# drownAlert_try1.net
KiCad netlist of a schematic drawn in EAGLE
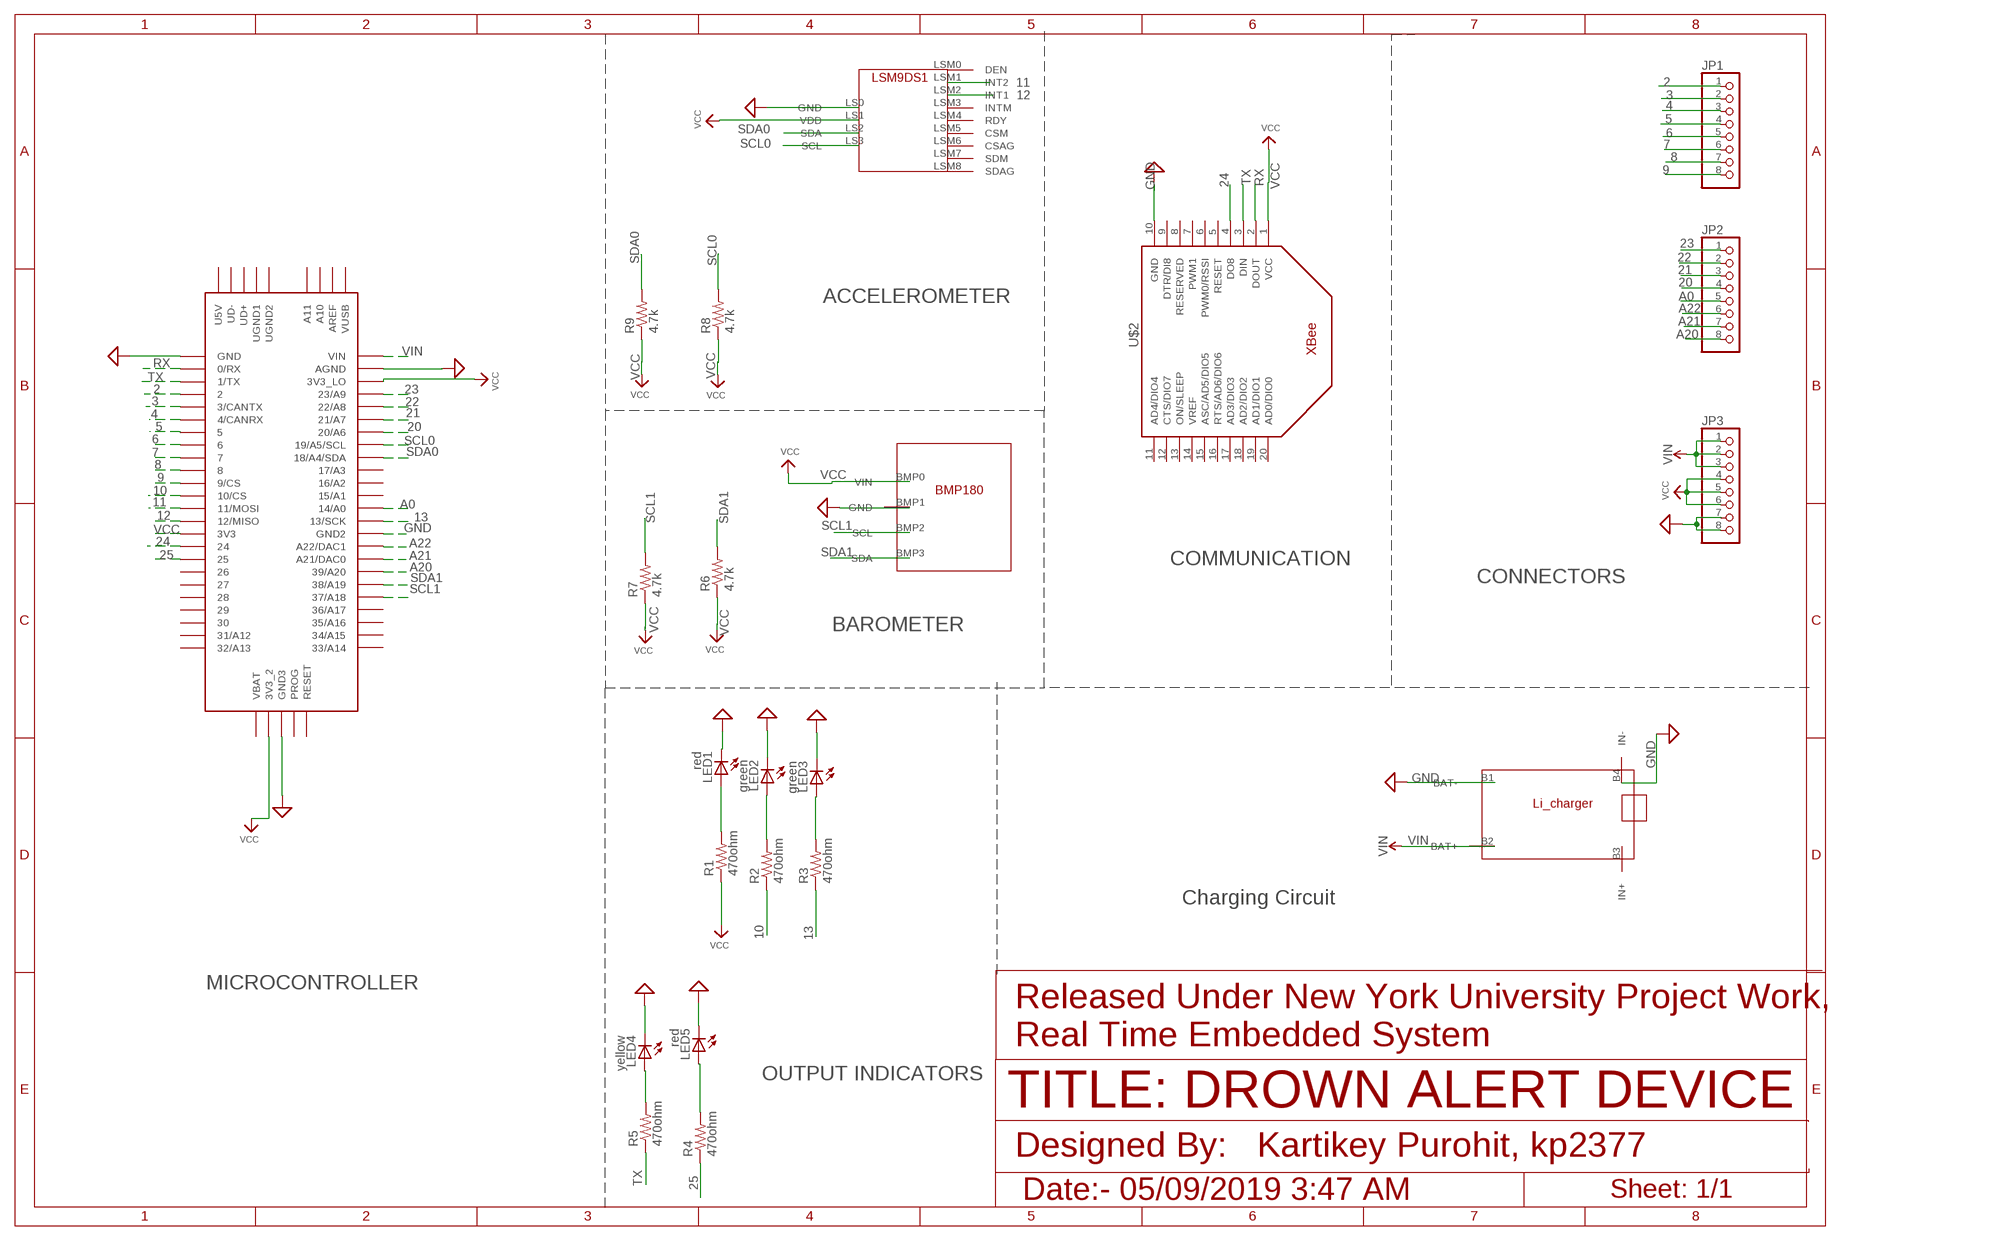
[diagram p0: schematic, sheet 1]

(export (version "E")
  (design (tool "Eeschema 10.0.6"))
  (components
    (comp (ref "JP1")
      (value "PINHD-1X8-3.5MM")
      (footprint "eagle-import:1X08-3.5MM")
      (libsource (lib "eagle-import") (part "PINHD-1X8-3.5MM"))
    )
    (comp (ref "JP2")
      (value "PINHD-1X8-3.5MM")
      (footprint "eagle-import:1X08-3.5MM")
      (libsource (lib "eagle-import") (part "PINHD-1X8-3.5MM"))
    )
    (comp (ref "JP3")
      (value "PINHD-1X8-3.5MM")
      (footprint "eagle-import:1X08-3.5MM")
      (libsource (lib "eagle-import") (part "PINHD-1X8-3.5MM"))
    )
    (comp (ref "LED1")
      (value "red")
      (footprint "eagle-import:CHIPLED_1206")
      (libsource (lib "eagle-import") (part "LEDCHIPLED_1206"))
    )
    (comp (ref "LED2")
      (value "green")
      (footprint "eagle-import:CHIPLED_1206")
      (libsource (lib "eagle-import") (part "LEDCHIPLED_1206"))
    )
    (comp (ref "LED3")
      (value "green")
      (footprint "eagle-import:CHIPLED_1206")
      (libsource (lib "eagle-import") (part "LEDCHIPLED_1206"))
    )
    (comp (ref "LED4")
      (value "yellow")
      (footprint "eagle-import:CHIPLED_1206")
      (libsource (lib "eagle-import") (part "LEDCHIPLED_1206"))
    )
    (comp (ref "LED5")
      (value "red")
      (footprint "eagle-import:CHIPLED_1206")
      (libsource (lib "eagle-import") (part "LEDCHIPLED_1206"))
    )
    (comp (ref "R1")
      (value "470ohm")
      (footprint "eagle-import:R1206")
      (libsource (lib "eagle-import") (part "R-US_R1206"))
    )
    (comp (ref "R2")
      (value "470ohm")
      (footprint "eagle-import:R1206")
      (libsource (lib "eagle-import") (part "R-US_R1206"))
    )
    (comp (ref "R3")
      (value "470ohm")
      (footprint "eagle-import:R1206")
      (libsource (lib "eagle-import") (part "R-US_R1206"))
    )
    (comp (ref "R4")
      (value "470ohm")
      (footprint "eagle-import:R1206")
      (libsource (lib "eagle-import") (part "R-US_R1206"))
    )
    (comp (ref "R5")
      (value "470ohm")
      (footprint "eagle-import:R1206")
      (libsource (lib "eagle-import") (part "R-US_R1206"))
    )
    (comp (ref "R6")
      (value "4.7k")
      (footprint "eagle-import:R1206")
      (libsource (lib "eagle-import") (part "R-US_R1206"))
    )
    (comp (ref "R7")
      (value "4.7k")
      (footprint "eagle-import:R1206")
      (libsource (lib "eagle-import") (part "R-US_R1206"))
    )
    (comp (ref "R8")
      (value "4.7k")
      (footprint "eagle-import:R1206")
      (libsource (lib "eagle-import") (part "R-US_R1206"))
    )
    (comp (ref "R9")
      (value "4.7k")
      (footprint "eagle-import:R1206")
      (libsource (lib "eagle-import") (part "R-US_R1206"))
    )
    (comp (ref "U$1")
      (value "TEENSY_3.5/3.6")
      (footprint "eagle-import:TEENSY_3.5_3.6")
      (libsource (lib "eagle-import") (part "TEENSY_3.5/3.6"))
    )
    (comp (ref "U$2")
      (value "XBEE")
      (footprint "eagle-import:XBEE")
      (libsource (lib "eagle-import") (part "XBEE"))
    )
    (comp (ref "U$3")
      (value "KKP_BATTERY_CHARGER")
      (footprint "eagle-import:KKP_CUSTOM_BATTERY_CHARGER")
      (libsource (lib "eagle-import") (part "KKP_BATTERY_CHARGER"))
    )
    (comp (ref "U$5")
      (value "KKP_BMP180")
      (footprint "eagle-import:KKP_CUSTOM_BMP180")
      (libsource (lib "eagle-import") (part "KKP_BMP180"))
    )
    (comp (ref "U$6")
      (value "KKP_LSM")
      (footprint "eagle-import:KKP_CUSTOM_LSM9D-S1_FOOTPRINT")
      (libsource (lib "eagle-import") (part "KKP_LSM"))
    )
  )
  (nets
    (net (code "1") (name "/2") (class "Default")
      (node (ref "JP1") (pin "1") (pinfunction "1_1") (pintype "passive"))
      (node (ref "U$1") (pin "2") (pinfunction "2_2") (pintype "bidirectional"))
    )
    (net (code "2") (name "/3") (class "Default")
      (node (ref "JP1") (pin "2") (pinfunction "2_2") (pintype "passive"))
      (node (ref "U$1") (pin "3/CANTX") (pinfunction "3/CANTX_3/CANTX") (pintype "bidirectional"))
    )
    (net (code "3") (name "/4") (class "Default")
      (node (ref "JP1") (pin "3") (pinfunction "3_3") (pintype "passive"))
      (node (ref "U$1") (pin "4/CANRX") (pinfunction "4/CANRX_4/CANRX") (pintype "bidirectional"))
    )
    (net (code "4") (name "/5") (class "Default")
      (node (ref "JP1") (pin "4") (pinfunction "4_4") (pintype "passive"))
      (node (ref "U$1") (pin "5") (pinfunction "5_5") (pintype "bidirectional"))
    )
    (net (code "5") (name "/6") (class "Default")
      (node (ref "JP1") (pin "5") (pinfunction "5_5") (pintype "passive"))
      (node (ref "U$1") (pin "6") (pinfunction "6_6") (pintype "bidirectional"))
    )
    (net (code "6") (name "/7") (class "Default")
      (node (ref "JP1") (pin "6") (pinfunction "6_6") (pintype "passive"))
      (node (ref "U$1") (pin "7") (pinfunction "7_7") (pintype "bidirectional"))
    )
    (net (code "7") (name "/8") (class "Default")
      (node (ref "JP1") (pin "7") (pinfunction "7_7") (pintype "passive"))
      (node (ref "U$1") (pin "8") (pinfunction "8_8") (pintype "bidirectional"))
    )
    (net (code "8") (name "/9") (class "Default")
      (node (ref "JP1") (pin "8") (pinfunction "8_8") (pintype "passive"))
      (node (ref "U$1") (pin "9/CS") (pinfunction "9/CS_9/CS") (pintype "bidirectional"))
    )
    (net (code "9") (name "/10") (class "Default")
      (node (ref "R2") (pin "1") (pinfunction "1_1") (pintype "passive"))
      (node (ref "U$1") (pin "10/CS") (pinfunction "10/CS_10/CS") (pintype "bidirectional"))
    )
    (net (code "10") (name "/11") (class "Default")
      (node (ref "U$1") (pin "11/MOSI") (pinfunction "11/MOSI_11/MOSI") (pintype "bidirectional"))
      (node (ref "U$6") (pin "LSM1") (pinfunction "INT2_LSM1") (pintype "bidirectional"))
    )
    (net (code "11") (name "/12") (class "Default")
      (node (ref "U$1") (pin "12/MISO") (pinfunction "12/MISO_12/MISO") (pintype "bidirectional"))
      (node (ref "U$6") (pin "LSM2") (pinfunction "INT1_LSM2") (pintype "bidirectional"))
    )
    (net (code "12") (name "/13") (class "Default")
      (node (ref "R3") (pin "1") (pinfunction "1_1") (pintype "passive"))
      (node (ref "U$1") (pin "13/SCK") (pinfunction "13/SCK_13/SCK") (pintype "bidirectional"))
    )
    (net (code "13") (name "/20") (class "Default")
      (node (ref "JP2") (pin "4") (pinfunction "4_4") (pintype "passive"))
      (node (ref "U$1") (pin "20/A6") (pinfunction "20/A6_20/A6") (pintype "bidirectional"))
    )
    (net (code "14") (name "/21") (class "Default")
      (node (ref "JP2") (pin "3") (pinfunction "3_3") (pintype "passive"))
      (node (ref "U$1") (pin "21/A7") (pinfunction "21/A7_21/A7") (pintype "bidirectional"))
    )
    (net (code "15") (name "/22") (class "Default")
      (node (ref "JP2") (pin "2") (pinfunction "2_2") (pintype "passive"))
      (node (ref "U$1") (pin "22/A8") (pinfunction "22/A8_22/A8") (pintype "bidirectional"))
    )
    (net (code "16") (name "/23") (class "Default")
      (node (ref "JP2") (pin "1") (pinfunction "1_1") (pintype "passive"))
      (node (ref "U$1") (pin "23/A9") (pinfunction "23/A9_23/A9") (pintype "bidirectional"))
    )
    (net (code "17") (name "/24") (class "Default")
      (node (ref "U$1") (pin "24") (pinfunction "24_24") (pintype "bidirectional"))
      (node (ref "U$2") (pin "4") (pinfunction "DO8_4") (pintype "output"))
    )
    (net (code "18") (name "/25") (class "Default")
      (node (ref "R4") (pin "1") (pinfunction "1_1") (pintype "passive"))
      (node (ref "U$1") (pin "25") (pinfunction "25_25") (pintype "bidirectional"))
    )
    (net (code "19") (name "/A0") (class "Default")
      (node (ref "JP2") (pin "5") (pinfunction "5_5") (pintype "passive"))
      (node (ref "U$1") (pin "14/A0") (pinfunction "14/A0_14/A0") (pintype "bidirectional"))
    )
    (net (code "20") (name "/A20") (class "Default")
      (node (ref "JP2") (pin "8") (pinfunction "8_8") (pintype "passive"))
      (node (ref "U$1") (pin "39/A20") (pinfunction "39/A20_39/A20") (pintype "bidirectional"))
    )
    (net (code "21") (name "/A21") (class "Default")
      (node (ref "JP2") (pin "7") (pinfunction "7_7") (pintype "passive"))
      (node (ref "U$1") (pin "21/DAC0") (pinfunction "A21/DAC0_21/DAC0") (pintype "bidirectional"))
    )
    (net (code "22") (name "/A22") (class "Default")
      (node (ref "JP2") (pin "6") (pinfunction "6_6") (pintype "passive"))
      (node (ref "U$1") (pin "A22/DAC1") (pinfunction "A22/DAC1_A22/DAC1") (pintype "bidirectional"))
    )
    (net (code "23") (name "/RX") (class "Default")
      (node (ref "U$1") (pin "0/RX") (pinfunction "0/RX_0/RX") (pintype "bidirectional"))
      (node (ref "U$2") (pin "2") (pinfunction "DOUT_2") (pintype "output"))
    )
    (net (code "24") (name "/SCL0") (class "Default")
      (node (ref "R8") (pin "2") (pinfunction "2_2") (pintype "passive"))
      (node (ref "U$1") (pin "19/A5/SCL") (pinfunction "19/A5/SCL_19/A5/SCL") (pintype "bidirectional"))
      (node (ref "U$6") (pin "LS3") (pinfunction "SCL_LS3") (pintype "bidirectional"))
    )
    (net (code "25") (name "/SCL1") (class "Default")
      (node (ref "R7") (pin "2") (pinfunction "2_2") (pintype "passive"))
      (node (ref "U$1") (pin "37/A18") (pinfunction "37/A18_37/A18") (pintype "bidirectional"))
      (node (ref "U$5") (pin "BMP2") (pinfunction "SCL_BMP2") (pintype "bidirectional"))
    )
    (net (code "26") (name "/SDA0") (class "Default")
      (node (ref "R9") (pin "2") (pinfunction "2_2") (pintype "passive"))
      (node (ref "U$1") (pin "18/A4/SDA") (pinfunction "18/A4/SDA_18/A4/SDA") (pintype "bidirectional"))
      (node (ref "U$6") (pin "LS2") (pinfunction "SDA_LS2") (pintype "bidirectional"))
    )
    (net (code "27") (name "/SDA1") (class "Default")
      (node (ref "R6") (pin "2") (pinfunction "2_2") (pintype "passive"))
      (node (ref "U$1") (pin "38/A19") (pinfunction "38/A19_38/A19") (pintype "bidirectional"))
      (node (ref "U$5") (pin "BMP3") (pinfunction "SDA_BMP3") (pintype "bidirectional"))
    )
    (net (code "28") (name "/TX") (class "Default")
      (node (ref "R5") (pin "1") (pinfunction "1_1") (pintype "passive"))
      (node (ref "U$1") (pin "1/TX") (pinfunction "1/TX_1/TX") (pintype "bidirectional"))
      (node (ref "U$2") (pin "3") (pinfunction "DIN_3") (pintype "input"))
    )
    (net (code "29") (name "Net-(LED1-PadA)") (class "Default")
      (node (ref "LED1") (pin "A") (pinfunction "A_A") (pintype "passive"))
      (node (ref "R1") (pin "2") (pinfunction "2_2") (pintype "passive"))
    )
    (net (code "30") (name "Net-(LED2-PadA)") (class "Default")
      (node (ref "LED2") (pin "A") (pinfunction "A_A") (pintype "passive"))
      (node (ref "R2") (pin "2") (pinfunction "2_2") (pintype "passive"))
    )
    (net (code "31") (name "Net-(LED3-PadA)") (class "Default")
      (node (ref "LED3") (pin "A") (pinfunction "A_A") (pintype "passive"))
      (node (ref "R3") (pin "2") (pinfunction "2_2") (pintype "passive"))
    )
    (net (code "32") (name "Net-(LED4-PadA)") (class "Default")
      (node (ref "LED4") (pin "A") (pinfunction "A_A") (pintype "passive"))
      (node (ref "R5") (pin "2") (pinfunction "2_2") (pintype "passive"))
    )
    (net (code "33") (name "Net-(LED5-PadA)") (class "Default")
      (node (ref "LED5") (pin "A") (pinfunction "A_A") (pintype "passive"))
      (node (ref "R4") (pin "2") (pinfunction "2_2") (pintype "passive"))
    )
    (net (code "34") (name "SUP") (class "Default")
      (node (ref "JP3") (pin "7") (pinfunction "7_7") (pintype "passive"))
      (node (ref "JP3") (pin "8") (pinfunction "8_8") (pintype "passive"))
      (node (ref "LED1") (pin "C") (pinfunction "C_C") (pintype "passive"))
      (node (ref "LED2") (pin "C") (pinfunction "C_C") (pintype "passive"))
      (node (ref "LED3") (pin "C") (pinfunction "C_C") (pintype "passive"))
      (node (ref "LED4") (pin "C") (pinfunction "C_C") (pintype "passive"))
      (node (ref "LED5") (pin "C") (pinfunction "C_C") (pintype "passive"))
      (node (ref "U$1") (pin "AGND") (pinfunction "AGND_AGND") (pintype "bidirectional"))
      (node (ref "U$1") (pin "GND") (pinfunction "GND_GND") (pintype "bidirectional"))
      (node (ref "U$1") (pin "GND2") (pinfunction "GND2_GND2") (pintype "bidirectional"))
      (node (ref "U$1") (pin "GND3") (pinfunction "GND3_GND3") (pintype "bidirectional"))
      (node (ref "U$2") (pin "10") (pinfunction "GND_10") (pintype "power_in"))
      (node (ref "U$3") (pin "B1") (pinfunction "BAT-_B1") (pintype "bidirectional"))
      (node (ref "U$3") (pin "B4") (pinfunction "IN-_B4") (pintype "bidirectional"))
      (node (ref "U$5") (pin "BMP1") (pinfunction "GND_BMP1") (pintype "bidirectional"))
      (node (ref "U$6") (pin "LS0") (pinfunction "GND_LS0") (pintype "bidirectional"))
    )
    (net (code "35") (name "VCC") (class "Default")
      (node (ref "JP3") (pin "4") (pinfunction "4_4") (pintype "passive"))
      (node (ref "JP3") (pin "5") (pinfunction "5_5") (pintype "passive"))
      (node (ref "JP3") (pin "6") (pinfunction "6_6") (pintype "passive"))
      (node (ref "R1") (pin "1") (pinfunction "1_1") (pintype "passive"))
      (node (ref "R6") (pin "1") (pinfunction "1_1") (pintype "passive"))
      (node (ref "R7") (pin "1") (pinfunction "1_1") (pintype "passive"))
      (node (ref "R8") (pin "1") (pinfunction "1_1") (pintype "passive"))
      (node (ref "R9") (pin "1") (pinfunction "1_1") (pintype "passive"))
      (node (ref "U$1") (pin "3V3") (pinfunction "3V3_3V3") (pintype "bidirectional"))
      (node (ref "U$1") (pin "3V3_2") (pinfunction "3V3_2_3V3_2") (pintype "bidirectional"))
      (node (ref "U$1") (pin "3V3_LO") (pinfunction "3V3_LO_3V3_LO") (pintype "bidirectional"))
      (node (ref "U$2") (pin "1") (pinfunction "VCC_1") (pintype "power_in"))
      (node (ref "U$5") (pin "BMP0") (pinfunction "VIN_BMP0") (pintype "bidirectional"))
      (node (ref "U$6") (pin "LS1") (pinfunction "VDD_LS1") (pintype "bidirectional"))
    )
    (net (code "36") (name "VIN") (class "Default")
      (node (ref "JP3") (pin "1") (pinfunction "1_1") (pintype "passive"))
      (node (ref "JP3") (pin "2") (pinfunction "2_2") (pintype "passive"))
      (node (ref "JP3") (pin "3") (pinfunction "3_3") (pintype "passive"))
      (node (ref "U$1") (pin "VIN") (pinfunction "VIN_VIN") (pintype "bidirectional"))
      (node (ref "U$3") (pin "B2") (pinfunction "BAT+_B2") (pintype "bidirectional"))
    )
    (net (code "37") (name "unconnected-(U$1-Pad15{slash}A1)") (class "Default")
      (node (ref "U$1") (pin "15/A1") (pinfunction "15/A1_15/A1") (pintype "bidirectional"))
    )
    (net (code "38") (name "unconnected-(U$1-Pad16{slash}A2)") (class "Default")
      (node (ref "U$1") (pin "16/A2") (pinfunction "16/A2_16/A2") (pintype "bidirectional"))
    )
    (net (code "39") (name "unconnected-(U$1-Pad17{slash}A3)") (class "Default")
      (node (ref "U$1") (pin "17/A3") (pinfunction "17/A3_17/A3") (pintype "bidirectional"))
    )
    (net (code "40") (name "unconnected-(U$1-Pad26)") (class "Default")
      (node (ref "U$1") (pin "26") (pinfunction "26_26") (pintype "bidirectional"))
    )
    (net (code "41") (name "unconnected-(U$1-Pad27)") (class "Default")
      (node (ref "U$1") (pin "27") (pinfunction "27_27") (pintype "bidirectional"))
    )
    (net (code "42") (name "unconnected-(U$1-Pad28)") (class "Default")
      (node (ref "U$1") (pin "28") (pinfunction "28_28") (pintype "bidirectional"))
    )
    (net (code "43") (name "unconnected-(U$1-Pad29)") (class "Default")
      (node (ref "U$1") (pin "29") (pinfunction "29_29") (pintype "bidirectional"))
    )
    (net (code "44") (name "unconnected-(U$1-Pad30)") (class "Default")
      (node (ref "U$1") (pin "30") (pinfunction "30_30") (pintype "bidirectional"))
    )
    (net (code "45") (name "unconnected-(U$1-Pad31{slash}A12)") (class "Default")
      (node (ref "U$1") (pin "31/A12") (pinfunction "31/A12_31/A12") (pintype "bidirectional"))
    )
    (net (code "46") (name "unconnected-(U$1-Pad32{slash}A13)") (class "Default")
      (node (ref "U$1") (pin "32/A13") (pinfunction "32/A13_32/A13") (pintype "bidirectional"))
    )
    (net (code "47") (name "unconnected-(U$1-Pad33{slash}A14)") (class "Default")
      (node (ref "U$1") (pin "33/A14") (pinfunction "33/A14_33/A14") (pintype "bidirectional"))
    )
    (net (code "48") (name "unconnected-(U$1-Pad34{slash}A15)") (class "Default")
      (node (ref "U$1") (pin "34/A15") (pinfunction "34/A15_34/A15") (pintype "bidirectional"))
    )
    (net (code "49") (name "unconnected-(U$1-Pad35{slash}A16)") (class "Default")
      (node (ref "U$1") (pin "35/A16") (pinfunction "35/A16_35/A16") (pintype "bidirectional"))
    )
    (net (code "50") (name "unconnected-(U$1-Pad36{slash}A17)") (class "Default")
      (node (ref "U$1") (pin "36/A17") (pinfunction "36/A17_36/A17") (pintype "bidirectional"))
    )
    (net (code "51") (name "unconnected-(U$1-PadA10)") (class "Default")
      (node (ref "U$1") (pin "A10") (pinfunction "A10_A10") (pintype "bidirectional"))
    )
    (net (code "52") (name "unconnected-(U$1-PadA11)") (class "Default")
      (node (ref "U$1") (pin "A11") (pinfunction "A11_A11") (pintype "bidirectional"))
    )
    (net (code "53") (name "unconnected-(U$1-PadAREF)") (class "Default")
      (node (ref "U$1") (pin "AREF") (pinfunction "AREF_AREF") (pintype "bidirectional"))
    )
    (net (code "54") (name "unconnected-(U$1-PadPROG)") (class "Default")
      (node (ref "U$1") (pin "PROG") (pinfunction "PROG_PROG") (pintype "bidirectional"))
    )
    (net (code "55") (name "unconnected-(U$1-PadRESET)") (class "Default")
      (node (ref "U$1") (pin "RESET") (pinfunction "RESET_RESET") (pintype "bidirectional"))
    )
    (net (code "56") (name "unconnected-(U$1-PadU5V)") (class "Default")
      (node (ref "U$1") (pin "U5V") (pinfunction "U5V_U5V") (pintype "bidirectional"))
    )
    (net (code "57") (name "unconnected-(U$1-PadUD+)") (class "Default")
      (node (ref "U$1") (pin "UD+") (pinfunction "UD+_UD+") (pintype "bidirectional"))
    )
    (net (code "58") (name "unconnected-(U$1-PadUD-)") (class "Default")
      (node (ref "U$1") (pin "UD-") (pinfunction "UD-_UD-") (pintype "bidirectional"))
    )
    (net (code "59") (name "unconnected-(U$1-PadUGND1)") (class "Default")
      (node (ref "U$1") (pin "UGND1") (pinfunction "UGND1_UGND1") (pintype "bidirectional"))
    )
    (net (code "60") (name "unconnected-(U$1-PadUGND2)") (class "Default")
      (node (ref "U$1") (pin "UGND2") (pinfunction "UGND2_UGND2") (pintype "bidirectional"))
    )
    (net (code "61") (name "unconnected-(U$1-PadVBAT)") (class "Default")
      (node (ref "U$1") (pin "VBAT") (pinfunction "VBAT_VBAT") (pintype "bidirectional"))
    )
    (net (code "62") (name "unconnected-(U$1-PadVUSB)") (class "Default")
      (node (ref "U$1") (pin "VUSB") (pinfunction "VUSB_VUSB") (pintype "bidirectional"))
    )
    (net (code "63") (name "unconnected-(U$2-AD0{slash}DIO0-Pad20)") (class "Default")
      (node (ref "U$2") (pin "20") (pinfunction "AD0/DIO0_20") (pintype "bidirectional"))
    )
    (net (code "64") (name "unconnected-(U$2-AD1{slash}DIO1-Pad19)") (class "Default")
      (node (ref "U$2") (pin "19") (pinfunction "AD1/DIO1_19") (pintype "bidirectional"))
    )
    (net (code "65") (name "unconnected-(U$2-AD2{slash}DIO2-Pad18)") (class "Default")
      (node (ref "U$2") (pin "18") (pinfunction "AD2/DIO2_18") (pintype "bidirectional"))
    )
    (net (code "66") (name "unconnected-(U$2-AD3{slash}DIO3-Pad17)") (class "Default")
      (node (ref "U$2") (pin "17") (pinfunction "AD3/DIO3_17") (pintype "bidirectional"))
    )
    (net (code "67") (name "unconnected-(U$2-AD4{slash}DIO4-Pad11)") (class "Default")
      (node (ref "U$2") (pin "11") (pinfunction "AD4/DIO4_11") (pintype "bidirectional"))
    )
    (net (code "68") (name "unconnected-(U$2-ASC{slash}AD5{slash}DIO5-Pad15)") (class "Default")
      (node (ref "U$2") (pin "15") (pinfunction "ASC/AD5/DIO5_15") (pintype "bidirectional"))
    )
    (net (code "69") (name "unconnected-(U$2-CTS{slash}DIO7-Pad12)") (class "Default")
      (node (ref "U$2") (pin "12") (pinfunction "CTS/DIO7_12") (pintype "bidirectional"))
    )
    (net (code "70") (name "unconnected-(U$2-DTR{slash}DI8-Pad9)") (class "Default")
      (node (ref "U$2") (pin "9") (pinfunction "DTR/DI8_9") (pintype "input"))
    )
    (net (code "71") (name "unconnected-(U$2-ON{slash}SLEEP-Pad13)") (class "Default")
      (node (ref "U$2") (pin "13") (pinfunction "ON/SLEEP_13") (pintype "output"))
    )
    (net (code "72") (name "unconnected-(U$2-PWM0{slash}RSSI-Pad6)") (class "Default")
      (node (ref "U$2") (pin "6") (pinfunction "PWM0/RSSI_6") (pintype "output"))
    )
    (net (code "73") (name "unconnected-(U$2-PWM1-Pad7)") (class "Default")
      (node (ref "U$2") (pin "7") (pinfunction "PWM1_7") (pintype "output"))
    )
    (net (code "74") (name "unconnected-(U$2-RESERVED-Pad8)") (class "Default")
      (node (ref "U$2") (pin "8") (pinfunction "RESERVED_8") (pintype "no_connect"))
    )
    (net (code "75") (name "unconnected-(U$2-RESET-Pad5)") (class "Default")
      (node (ref "U$2") (pin "5") (pinfunction "RESET_5") (pintype "input"))
    )
    (net (code "76") (name "unconnected-(U$2-RTS{slash}AD6{slash}DIO6-Pad16)") (class "Default")
      (node (ref "U$2") (pin "16") (pinfunction "RTS/AD6/DIO6_16") (pintype "bidirectional"))
    )
    (net (code "77") (name "unconnected-(U$2-VREF-Pad14)") (class "Default")
      (node (ref "U$2") (pin "14") (pinfunction "VREF_14") (pintype "input"))
    )
    (net (code "78") (name "unconnected-(U$3-IN+-PadB3)") (class "Default")
      (node (ref "U$3") (pin "B3") (pinfunction "IN+_B3") (pintype "bidirectional"))
    )
    (net (code "79") (name "unconnected-(U$6-CSAG-PadLSM6)") (class "Default")
      (node (ref "U$6") (pin "LSM6") (pinfunction "CSAG_LSM6") (pintype "bidirectional"))
    )
    (net (code "80") (name "unconnected-(U$6-CSM-PadLSM5)") (class "Default")
      (node (ref "U$6") (pin "LSM5") (pinfunction "CSM_LSM5") (pintype "bidirectional"))
    )
    (net (code "81") (name "unconnected-(U$6-DEN-PadLSM0)") (class "Default")
      (node (ref "U$6") (pin "LSM0") (pinfunction "DEN_LSM0") (pintype "bidirectional"))
    )
    (net (code "82") (name "unconnected-(U$6-INTM-PadLSM3)") (class "Default")
      (node (ref "U$6") (pin "LSM3") (pinfunction "INTM_LSM3") (pintype "bidirectional"))
    )
    (net (code "83") (name "unconnected-(U$6-RDY-PadLSM4)") (class "Default")
      (node (ref "U$6") (pin "LSM4") (pinfunction "RDY_LSM4") (pintype "bidirectional"))
    )
    (net (code "84") (name "unconnected-(U$6-SDAG-PadLSM8)") (class "Default")
      (node (ref "U$6") (pin "LSM8") (pinfunction "SDAG_LSM8") (pintype "bidirectional"))
    )
    (net (code "85") (name "unconnected-(U$6-SDM-PadLSM7)") (class "Default")
      (node (ref "U$6") (pin "LSM7") (pinfunction "SDM_LSM7") (pintype "bidirectional"))
    )
  )
)
